# RGB_Controller.net
KiCad netlist of a schematic drawn in EAGLE
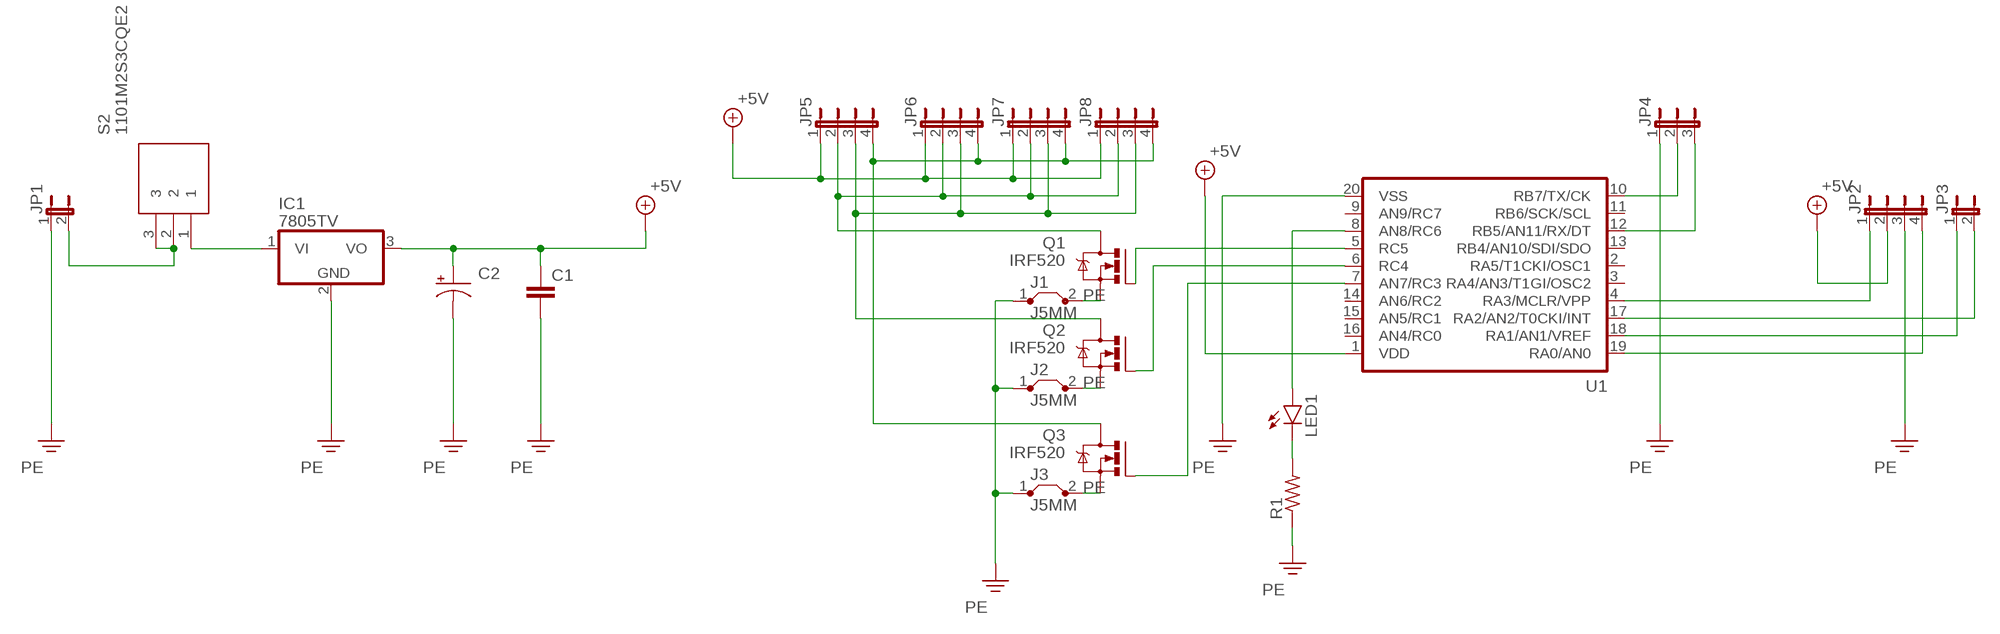
[diagram p0: schematic, sheet 1]

(export (version "E")
  (design (tool "Eeschema 10.0.6"))
  (components
    (comp (ref "C1")
      (value "C-EU025-024X044")
      (footprint "eagle-import:C025-024X044")
      (libsource (lib "eagle-import") (part "C-EU025-024X044"))
    )
    (comp (ref "C2")
      (value "CPOL-USE3.5-10")
      (footprint "eagle-import:E3,5-10")
      (libsource (lib "eagle-import") (part "CPOL-USE3.5-10"))
    )
    (comp (ref "IC1")
      (value "7805TV")
      (footprint "eagle-import:TO220V")
      (libsource (lib "eagle-import") (part "78TV05"))
    )
    (comp (ref "J1")
      (value "J5MM")
      (footprint "eagle-import:05")
      (libsource (lib "eagle-import") (part "J5MM"))
    )
    (comp (ref "J2")
      (value "J5MM")
      (footprint "eagle-import:05")
      (libsource (lib "eagle-import") (part "J5MM"))
    )
    (comp (ref "J3")
      (value "J5MM")
      (footprint "eagle-import:05")
      (libsource (lib "eagle-import") (part "J5MM"))
    )
    (comp (ref "JP1")
      (value "JP1E")
      (footprint "eagle-import:JP1")
      (libsource (lib "eagle-import") (part "JP1E"))
    )
    (comp (ref "JP2")
      (value "JP4E")
      (footprint "eagle-import:JP4")
      (libsource (lib "eagle-import") (part "JP4E"))
    )
    (comp (ref "JP3")
      (value "JP1E")
      (footprint "eagle-import:JP1")
      (libsource (lib "eagle-import") (part "JP1E"))
    )
    (comp (ref "JP4")
      (value "JP2E")
      (footprint "eagle-import:JP2")
      (libsource (lib "eagle-import") (part "JP2E"))
    )
    (comp (ref "JP5")
      (value "JP4E")
      (footprint "eagle-import:JP4")
      (libsource (lib "eagle-import") (part "JP4E"))
    )
    (comp (ref "JP6")
      (value "JP4E")
      (footprint "eagle-import:JP4")
      (libsource (lib "eagle-import") (part "JP4E"))
    )
    (comp (ref "JP7")
      (value "JP4E")
      (footprint "eagle-import:JP4")
      (libsource (lib "eagle-import") (part "JP4E"))
    )
    (comp (ref "JP8")
      (value "JP4E")
      (footprint "eagle-import:JP4")
      (libsource (lib "eagle-import") (part "JP4E"))
    )
    (comp (ref "LED1")
      (value "LED5MM")
      (footprint "eagle-import:LED5MM")
      (libsource (lib "eagle-import") (part "LED5MM"))
    )
    (comp (ref "Q1")
      (value "IRF520")
      (footprint "eagle-import:TO220BV")
      (libsource (lib "eagle-import") (part "IRF520"))
    )
    (comp (ref "Q2")
      (value "IRF520")
      (footprint "eagle-import:TO220BV")
      (libsource (lib "eagle-import") (part "IRF520"))
    )
    (comp (ref "Q3")
      (value "IRF520")
      (footprint "eagle-import:TO220BV")
      (libsource (lib "eagle-import") (part "IRF520"))
    )
    (comp (ref "R1")
      (value "R-US_0207/10")
      (footprint "eagle-import:0207_10")
      (libsource (lib "eagle-import") (part "R-US_0207/10"))
    )
    (comp (ref "S2")
      (value "1101M2S3CQE2")
      (footprint "eagle-import:1000-SERIES(SPDT)")
      (fields (field (name "MOUSER_PART_NUMBER") "611-1101M2S3CQE2"))
      (libsource (lib "eagle-import") (part "1101M2S3CQE2"))
    )
    (comp (ref "U1")
      (value "PIC16F6XX")
      (footprint "eagle-import:DIL20")
      (libsource (lib "eagle-import") (part "PIC16F6XX"))
    )
  )
  (nets
    (net (code "1") (name "+5V") (class "Default")
      (node (ref "C1") (pin "1") (pinfunction "1_1") (pintype "passive"))
      (node (ref "C2") (pin "+") (pinfunction "+_+") (pintype "passive"))
      (node (ref "IC1") (pin "3") (pinfunction "VO_3") (pintype "passive"))
      (node (ref "JP2") (pin "2") (pinfunction "2_2") (pintype "passive"))
      (node (ref "JP5") (pin "1") (pinfunction "1_1") (pintype "passive"))
      (node (ref "JP6") (pin "1") (pinfunction "1_1") (pintype "passive"))
      (node (ref "JP7") (pin "1") (pinfunction "1_1") (pintype "passive"))
      (node (ref "JP8") (pin "1") (pinfunction "1_1") (pintype "passive"))
      (node (ref "U1") (pin "1") (pinfunction "VDD_1") (pintype "power_in"))
    )
    (net (code "2") (name "Net-(IC1-VI)") (class "Default")
      (node (ref "IC1") (pin "1") (pinfunction "VI_1") (pintype "input"))
      (node (ref "S2") (pin "1") (pinfunction "1_1") (pintype "bidirectional"))
    )
    (net (code "3") (name "Net-(JP1-Pad2)") (class "Default")
      (node (ref "JP1") (pin "2") (pinfunction "2_2") (pintype "passive"))
      (node (ref "S2") (pin "2") (pinfunction "2_2") (pintype "bidirectional"))
      (node (ref "S2") (pin "3") (pinfunction "3_3") (pintype "bidirectional"))
    )
    (net (code "4") (name "Net-(JP5-Pad2)") (class "Default")
      (node (ref "JP5") (pin "2") (pinfunction "2_2") (pintype "passive"))
      (node (ref "JP6") (pin "2") (pinfunction "2_2") (pintype "passive"))
      (node (ref "JP7") (pin "2") (pinfunction "2_2") (pintype "passive"))
      (node (ref "JP8") (pin "2") (pinfunction "2_2") (pintype "passive"))
      (node (ref "Q1") (pin "D") (pinfunction "D_D") (pintype "passive"))
    )
    (net (code "5") (name "Net-(JP5-Pad3)") (class "Default")
      (node (ref "JP5") (pin "3") (pinfunction "3_3") (pintype "passive"))
      (node (ref "JP6") (pin "3") (pinfunction "3_3") (pintype "passive"))
      (node (ref "JP7") (pin "3") (pinfunction "3_3") (pintype "passive"))
      (node (ref "JP8") (pin "3") (pinfunction "3_3") (pintype "passive"))
      (node (ref "Q2") (pin "D") (pinfunction "D_D") (pintype "passive"))
    )
    (net (code "6") (name "Net-(JP5-Pad4)") (class "Default")
      (node (ref "JP5") (pin "4") (pinfunction "4_4") (pintype "passive"))
      (node (ref "JP6") (pin "4") (pinfunction "4_4") (pintype "passive"))
      (node (ref "JP7") (pin "4") (pinfunction "4_4") (pintype "passive"))
      (node (ref "JP8") (pin "4") (pinfunction "4_4") (pintype "passive"))
      (node (ref "Q3") (pin "D") (pinfunction "D_D") (pintype "passive"))
    )
    (net (code "7") (name "Net-(LED1-C)") (class "Default")
      (node (ref "LED1") (pin "K") (pinfunction "C_K") (pintype "passive"))
      (node (ref "R1") (pin "2") (pinfunction "2_2") (pintype "passive"))
    )
    (net (code "8") (name "Net-(U1-AN7{slash}RC3)") (class "Default")
      (node (ref "Q3") (pin "G") (pinfunction "G_G") (pintype "passive"))
      (node (ref "U1") (pin "7") (pinfunction "AN7/RC3_7") (pintype "bidirectional"))
    )
    (net (code "9") (name "Net-(U1-AN8{slash}RC6)") (class "Default")
      (node (ref "LED1") (pin "A") (pinfunction "A_A") (pintype "passive"))
      (node (ref "U1") (pin "8") (pinfunction "AN8/RC6_8") (pintype "bidirectional"))
    )
    (net (code "10") (name "Net-(U1-RA0{slash}AN0)") (class "Default")
      (node (ref "JP2") (pin "4") (pinfunction "4_4") (pintype "passive"))
      (node (ref "U1") (pin "19") (pinfunction "RA0/AN0_19") (pintype "bidirectional"))
    )
    (net (code "11") (name "Net-(U1-RA1{slash}AN1{slash}VREF)") (class "Default")
      (node (ref "JP3") (pin "1") (pinfunction "1_1") (pintype "passive"))
      (node (ref "U1") (pin "18") (pinfunction "RA1/AN1/VREF_18") (pintype "bidirectional"))
    )
    (net (code "12") (name "Net-(U1-RA2{slash}AN2{slash}T0CKI{slash}INT)") (class "Default")
      (node (ref "JP3") (pin "2") (pinfunction "2_2") (pintype "passive"))
      (node (ref "U1") (pin "17") (pinfunction "RA2/AN2/T0CKI/INT_17") (pintype "bidirectional"))
    )
    (net (code "13") (name "Net-(U1-RA3{slash}MCLR{slash}VPP)") (class "Default")
      (node (ref "JP2") (pin "1") (pinfunction "1_1") (pintype "passive"))
      (node (ref "U1") (pin "4") (pinfunction "RA3/MCLR/VPP_4") (pintype "input"))
    )
    (net (code "14") (name "Net-(U1-RB5{slash}AN11{slash}RX{slash}DT)") (class "Default")
      (node (ref "JP4") (pin "3") (pinfunction "3_3") (pintype "passive"))
      (node (ref "U1") (pin "12") (pinfunction "RB5/AN11/RX/DT_12") (pintype "bidirectional"))
    )
    (net (code "15") (name "Net-(U1-RB7{slash}TX{slash}CK)") (class "Default")
      (node (ref "JP4") (pin "2") (pinfunction "2_2") (pintype "passive"))
      (node (ref "U1") (pin "10") (pinfunction "RB7/TX/CK_10") (pintype "bidirectional"))
    )
    (net (code "16") (name "Net-(U1-RC4)") (class "Default")
      (node (ref "Q2") (pin "G") (pinfunction "G_G") (pintype "passive"))
      (node (ref "U1") (pin "6") (pinfunction "RC4_6") (pintype "bidirectional"))
    )
    (net (code "17") (name "Net-(U1-RC5)") (class "Default")
      (node (ref "Q1") (pin "G") (pinfunction "G_G") (pintype "passive"))
      (node (ref "U1") (pin "5") (pinfunction "RC5_5") (pintype "bidirectional"))
    )
    (net (code "18") (name "PE") (class "Default")
      (node (ref "C1") (pin "2") (pinfunction "2_2") (pintype "passive"))
      (node (ref "C2") (pin "-") (pinfunction "-_-") (pintype "passive"))
      (node (ref "IC1") (pin "2") (pinfunction "GND_2") (pintype "passive"))
      (node (ref "J1") (pin "1") (pinfunction "1_1") (pintype "passive"))
      (node (ref "J1") (pin "2") (pinfunction "2_2") (pintype "passive"))
      (node (ref "J2") (pin "1") (pinfunction "1_1") (pintype "passive"))
      (node (ref "J2") (pin "2") (pinfunction "2_2") (pintype "passive"))
      (node (ref "J3") (pin "1") (pinfunction "1_1") (pintype "passive"))
      (node (ref "J3") (pin "2") (pinfunction "2_2") (pintype "passive"))
      (node (ref "JP1") (pin "1") (pinfunction "1_1") (pintype "passive"))
      (node (ref "JP2") (pin "3") (pinfunction "3_3") (pintype "passive"))
      (node (ref "JP4") (pin "1") (pinfunction "1_1") (pintype "passive"))
      (node (ref "Q1") (pin "S") (pinfunction "S_S") (pintype "passive"))
      (node (ref "Q2") (pin "S") (pinfunction "S_S") (pintype "passive"))
      (node (ref "Q3") (pin "S") (pinfunction "S_S") (pintype "passive"))
      (node (ref "R1") (pin "1") (pinfunction "1_1") (pintype "passive"))
      (node (ref "U1") (pin "20") (pinfunction "VSS_20") (pintype "power_in"))
    )
    (net (code "19") (name "unconnected-(U1-AN4{slash}RC0-Pad16)") (class "Default")
      (node (ref "U1") (pin "16") (pinfunction "AN4/RC0_16") (pintype "bidirectional"))
    )
    (net (code "20") (name "unconnected-(U1-AN5{slash}RC1-Pad15)") (class "Default")
      (node (ref "U1") (pin "15") (pinfunction "AN5/RC1_15") (pintype "bidirectional"))
    )
    (net (code "21") (name "unconnected-(U1-AN6{slash}RC2-Pad14)") (class "Default")
      (node (ref "U1") (pin "14") (pinfunction "AN6/RC2_14") (pintype "bidirectional"))
    )
    (net (code "22") (name "unconnected-(U1-AN9{slash}RC7-Pad9)") (class "Default")
      (node (ref "U1") (pin "9") (pinfunction "AN9/RC7_9") (pintype "bidirectional"))
    )
    (net (code "23") (name "unconnected-(U1-RA4{slash}AN3{slash}T1GI{slash}OSC2-Pad3)") (class "Default")
      (node (ref "U1") (pin "3") (pinfunction "RA4/AN3/T1GI/OSC2_3") (pintype "bidirectional"))
    )
    (net (code "24") (name "unconnected-(U1-RA5{slash}T1CKI{slash}OSC1-Pad2)") (class "Default")
      (node (ref "U1") (pin "2") (pinfunction "RA5/T1CKI/OSC1_2") (pintype "bidirectional"))
    )
    (net (code "25") (name "unconnected-(U1-RB4{slash}AN10{slash}SDI{slash}SDO-Pad13)") (class "Default")
      (node (ref "U1") (pin "13") (pinfunction "RB4/AN10/SDI/SDO_13") (pintype "bidirectional"))
    )
    (net (code "26") (name "unconnected-(U1-RB6{slash}SCK{slash}SCL-Pad11)") (class "Default")
      (node (ref "U1") (pin "11") (pinfunction "RB6/SCK/SCL_11") (pintype "bidirectional"))
    )
  )
)
